# UVB_LED_Array.net
KiCad netlist of a schematic drawn in Altium Designer
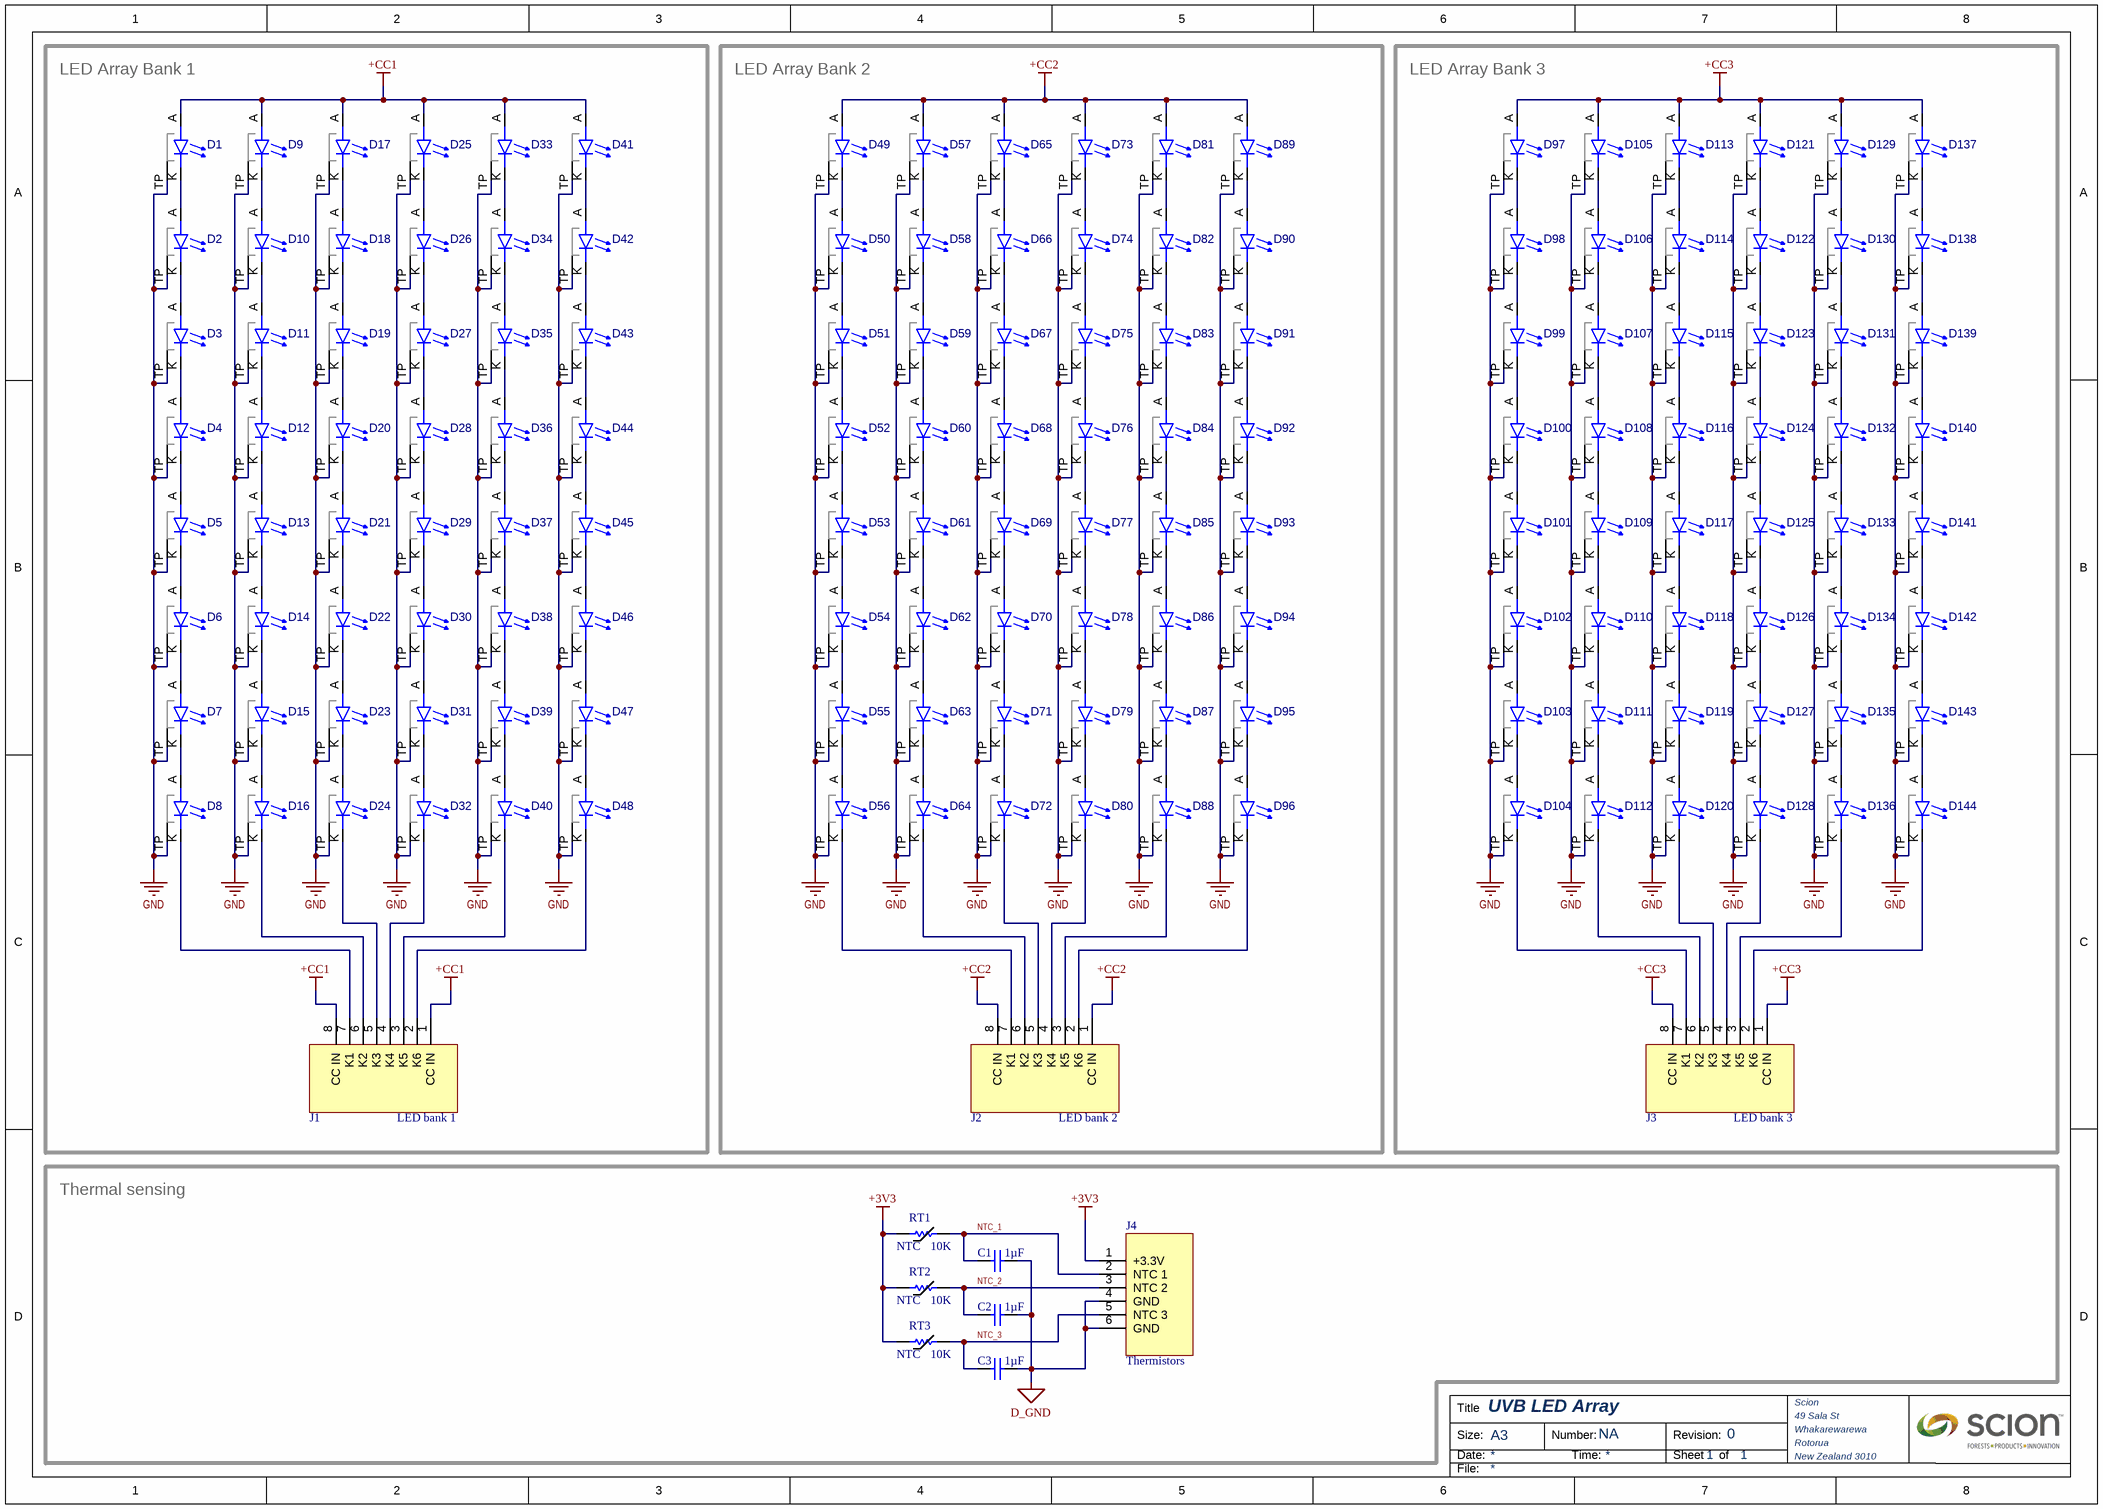
[diagram p0: UVB LED Array.SchDoc]

(export (version "E")
  (design (tool "Eeschema 10.0.6"))
  (components
    (comp (ref "C1")
      (value "1µF")
      (footprint "0603_CAP")
      (description "SMD Capacitor")
      (fields (field (name "Comment") "Capacitor"))
      (libsource (lib "Scion Research") (part "CMP-019-00005-2"))
    )
    (comp (ref "C2")
      (value "1µF")
      (footprint "0603_CAP")
      (description "SMD Capacitor")
      (fields (field (name "Comment") "Capacitor"))
      (libsource (lib "Scion Research") (part "CMP-019-00005-2"))
    )
    (comp (ref "C3")
      (value "1µF")
      (footprint "0603_CAP")
      (description "SMD Capacitor")
      (fields (field (name "Comment") "Capacitor"))
      (libsource (lib "Scion Research") (part "CMP-019-00005-2"))
    )
    (comp (ref "D1")
      (value "3838UVB UV SMD LED")
      (footprint "3838UVB UV SMD LED-Footprint-1")
      (libsource (lib "Scion Research") (part "UVB SMD LED"))
    )
    (comp (ref "D2")
      (value "3838UVB UV SMD LED")
      (footprint "3838UVB UV SMD LED-Footprint-1")
      (libsource (lib "Scion Research") (part "UVB SMD LED"))
    )
    (comp (ref "D3")
      (value "3838UVB UV SMD LED")
      (footprint "3838UVB UV SMD LED-Footprint-1")
      (libsource (lib "Scion Research") (part "UVB SMD LED"))
    )
    (comp (ref "D4")
      (value "3838UVB UV SMD LED")
      (footprint "3838UVB UV SMD LED-Footprint-1")
      (libsource (lib "Scion Research") (part "UVB SMD LED"))
    )
    (comp (ref "D5")
      (value "3838UVB UV SMD LED")
      (footprint "3838UVB UV SMD LED-Footprint-1")
      (libsource (lib "Scion Research") (part "UVB SMD LED"))
    )
    (comp (ref "D6")
      (value "3838UVB UV SMD LED")
      (footprint "3838UVB UV SMD LED-Footprint-1")
      (libsource (lib "Scion Research") (part "UVB SMD LED"))
    )
    (comp (ref "D7")
      (value "3838UVB UV SMD LED")
      (footprint "3838UVB UV SMD LED-Footprint-1")
      (libsource (lib "Scion Research") (part "UVB SMD LED"))
    )
    (comp (ref "D8")
      (value "3838UVB UV SMD LED")
      (footprint "3838UVB UV SMD LED-Footprint-1")
      (libsource (lib "Scion Research") (part "UVB SMD LED"))
    )
    (comp (ref "D9")
      (value "3838UVB UV SMD LED")
      (footprint "3838UVB UV SMD LED-Footprint-1")
      (libsource (lib "Scion Research") (part "UVB SMD LED"))
    )
    (comp (ref "D10")
      (value "3838UVB UV SMD LED")
      (footprint "3838UVB UV SMD LED-Footprint-1")
      (libsource (lib "Scion Research") (part "UVB SMD LED"))
    )
    (comp (ref "D11")
      (value "3838UVB UV SMD LED")
      (footprint "3838UVB UV SMD LED-Footprint-1")
      (libsource (lib "Scion Research") (part "UVB SMD LED"))
    )
    (comp (ref "D12")
      (value "3838UVB UV SMD LED")
      (footprint "3838UVB UV SMD LED-Footprint-1")
      (libsource (lib "Scion Research") (part "UVB SMD LED"))
    )
    (comp (ref "D13")
      (value "3838UVB UV SMD LED")
      (footprint "3838UVB UV SMD LED-Footprint-1")
      (libsource (lib "Scion Research") (part "UVB SMD LED"))
    )
    (comp (ref "D14")
      (value "3838UVB UV SMD LED")
      (footprint "3838UVB UV SMD LED-Footprint-1")
      (libsource (lib "Scion Research") (part "UVB SMD LED"))
    )
    (comp (ref "D15")
      (value "3838UVB UV SMD LED")
      (footprint "3838UVB UV SMD LED-Footprint-1")
      (libsource (lib "Scion Research") (part "UVB SMD LED"))
    )
    (comp (ref "D16")
      (value "3838UVB UV SMD LED")
      (footprint "3838UVB UV SMD LED-Footprint-1")
      (libsource (lib "Scion Research") (part "UVB SMD LED"))
    )
    (comp (ref "D17")
      (value "3838UVB UV SMD LED")
      (footprint "3838UVB UV SMD LED-Footprint-1")
      (libsource (lib "Scion Research") (part "UVB SMD LED"))
    )
    (comp (ref "D18")
      (value "3838UVB UV SMD LED")
      (footprint "3838UVB UV SMD LED-Footprint-1")
      (libsource (lib "Scion Research") (part "UVB SMD LED"))
    )
    (comp (ref "D19")
      (value "3838UVB UV SMD LED")
      (footprint "3838UVB UV SMD LED-Footprint-1")
      (libsource (lib "Scion Research") (part "UVB SMD LED"))
    )
    (comp (ref "D20")
      (value "3838UVB UV SMD LED")
      (footprint "3838UVB UV SMD LED-Footprint-1")
      (libsource (lib "Scion Research") (part "UVB SMD LED"))
    )
    (comp (ref "D21")
      (value "3838UVB UV SMD LED")
      (footprint "3838UVB UV SMD LED-Footprint-1")
      (libsource (lib "Scion Research") (part "UVB SMD LED"))
    )
    (comp (ref "D22")
      (value "3838UVB UV SMD LED")
      (footprint "3838UVB UV SMD LED-Footprint-1")
      (libsource (lib "Scion Research") (part "UVB SMD LED"))
    )
    (comp (ref "D23")
      (value "3838UVB UV SMD LED")
      (footprint "3838UVB UV SMD LED-Footprint-1")
      (libsource (lib "Scion Research") (part "UVB SMD LED"))
    )
    (comp (ref "D24")
      (value "3838UVB UV SMD LED")
      (footprint "3838UVB UV SMD LED-Footprint-1")
      (libsource (lib "Scion Research") (part "UVB SMD LED"))
    )
    (comp (ref "D25")
      (value "3838UVB UV SMD LED")
      (footprint "3838UVB UV SMD LED-Footprint-1")
      (libsource (lib "Scion Research") (part "UVB SMD LED"))
    )
    (comp (ref "D26")
      (value "3838UVB UV SMD LED")
      (footprint "3838UVB UV SMD LED-Footprint-1")
      (libsource (lib "Scion Research") (part "UVB SMD LED"))
    )
    (comp (ref "D27")
      (value "3838UVB UV SMD LED")
      (footprint "3838UVB UV SMD LED-Footprint-1")
      (libsource (lib "Scion Research") (part "UVB SMD LED"))
    )
    (comp (ref "D28")
      (value "3838UVB UV SMD LED")
      (footprint "3838UVB UV SMD LED-Footprint-1")
      (libsource (lib "Scion Research") (part "UVB SMD LED"))
    )
    (comp (ref "D29")
      (value "3838UVB UV SMD LED")
      (footprint "3838UVB UV SMD LED-Footprint-1")
      (libsource (lib "Scion Research") (part "UVB SMD LED"))
    )
    (comp (ref "D30")
      (value "3838UVB UV SMD LED")
      (footprint "3838UVB UV SMD LED-Footprint-1")
      (libsource (lib "Scion Research") (part "UVB SMD LED"))
    )
    (comp (ref "D31")
      (value "3838UVB UV SMD LED")
      (footprint "3838UVB UV SMD LED-Footprint-1")
      (libsource (lib "Scion Research") (part "UVB SMD LED"))
    )
    (comp (ref "D32")
      (value "3838UVB UV SMD LED")
      (footprint "3838UVB UV SMD LED-Footprint-1")
      (libsource (lib "Scion Research") (part "UVB SMD LED"))
    )
    (comp (ref "D33")
      (value "3838UVB UV SMD LED")
      (footprint "3838UVB UV SMD LED-Footprint-1")
      (libsource (lib "Scion Research") (part "UVB SMD LED"))
    )
    (comp (ref "D34")
      (value "3838UVB UV SMD LED")
      (footprint "3838UVB UV SMD LED-Footprint-1")
      (libsource (lib "Scion Research") (part "UVB SMD LED"))
    )
    (comp (ref "D35")
      (value "3838UVB UV SMD LED")
      (footprint "3838UVB UV SMD LED-Footprint-1")
      (libsource (lib "Scion Research") (part "UVB SMD LED"))
    )
    (comp (ref "D36")
      (value "3838UVB UV SMD LED")
      (footprint "3838UVB UV SMD LED-Footprint-1")
      (libsource (lib "Scion Research") (part "UVB SMD LED"))
    )
    (comp (ref "D37")
      (value "3838UVB UV SMD LED")
      (footprint "3838UVB UV SMD LED-Footprint-1")
      (libsource (lib "Scion Research") (part "UVB SMD LED"))
    )
    (comp (ref "D38")
      (value "3838UVB UV SMD LED")
      (footprint "3838UVB UV SMD LED-Footprint-1")
      (libsource (lib "Scion Research") (part "UVB SMD LED"))
    )
    (comp (ref "D39")
      (value "3838UVB UV SMD LED")
      (footprint "3838UVB UV SMD LED-Footprint-1")
      (libsource (lib "Scion Research") (part "UVB SMD LED"))
    )
    (comp (ref "D40")
      (value "3838UVB UV SMD LED")
      (footprint "3838UVB UV SMD LED-Footprint-1")
      (libsource (lib "Scion Research") (part "UVB SMD LED"))
    )
    (comp (ref "D41")
      (value "3838UVB UV SMD LED")
      (footprint "3838UVB UV SMD LED-Footprint-1")
      (libsource (lib "Scion Research") (part "UVB SMD LED"))
    )
    (comp (ref "D42")
      (value "3838UVB UV SMD LED")
      (footprint "3838UVB UV SMD LED-Footprint-1")
      (libsource (lib "Scion Research") (part "UVB SMD LED"))
    )
    (comp (ref "D43")
      (value "3838UVB UV SMD LED")
      (footprint "3838UVB UV SMD LED-Footprint-1")
      (libsource (lib "Scion Research") (part "UVB SMD LED"))
    )
    (comp (ref "D44")
      (value "3838UVB UV SMD LED")
      (footprint "3838UVB UV SMD LED-Footprint-1")
      (libsource (lib "Scion Research") (part "UVB SMD LED"))
    )
    (comp (ref "D45")
      (value "3838UVB UV SMD LED")
      (footprint "3838UVB UV SMD LED-Footprint-1")
      (libsource (lib "Scion Research") (part "UVB SMD LED"))
    )
    (comp (ref "D46")
      (value "3838UVB UV SMD LED")
      (footprint "3838UVB UV SMD LED-Footprint-1")
      (libsource (lib "Scion Research") (part "UVB SMD LED"))
    )
    (comp (ref "D47")
      (value "3838UVB UV SMD LED")
      (footprint "3838UVB UV SMD LED-Footprint-1")
      (libsource (lib "Scion Research") (part "UVB SMD LED"))
    )
    (comp (ref "D48")
      (value "3838UVB UV SMD LED")
      (footprint "3838UVB UV SMD LED-Footprint-1")
      (libsource (lib "Scion Research") (part "UVB SMD LED"))
    )
    (comp (ref "D49")
      (value "3838UVB UV SMD LED")
      (footprint "3838UVB UV SMD LED-Footprint-1")
      (libsource (lib "Scion Research") (part "UVB SMD LED"))
    )
    (comp (ref "D50")
      (value "3838UVB UV SMD LED")
      (footprint "3838UVB UV SMD LED-Footprint-1")
      (libsource (lib "Scion Research") (part "UVB SMD LED"))
    )
    (comp (ref "D51")
      (value "3838UVB UV SMD LED")
      (footprint "3838UVB UV SMD LED-Footprint-1")
      (libsource (lib "Scion Research") (part "UVB SMD LED"))
    )
    (comp (ref "D52")
      (value "3838UVB UV SMD LED")
      (footprint "3838UVB UV SMD LED-Footprint-1")
      (libsource (lib "Scion Research") (part "UVB SMD LED"))
    )
    (comp (ref "D53")
      (value "3838UVB UV SMD LED")
      (footprint "3838UVB UV SMD LED-Footprint-1")
      (libsource (lib "Scion Research") (part "UVB SMD LED"))
    )
    (comp (ref "D54")
      (value "3838UVB UV SMD LED")
      (footprint "3838UVB UV SMD LED-Footprint-1")
      (libsource (lib "Scion Research") (part "UVB SMD LED"))
    )
    (comp (ref "D55")
      (value "3838UVB UV SMD LED")
      (footprint "3838UVB UV SMD LED-Footprint-1")
      (libsource (lib "Scion Research") (part "UVB SMD LED"))
    )
    (comp (ref "D56")
      (value "3838UVB UV SMD LED")
      (footprint "3838UVB UV SMD LED-Footprint-1")
      (libsource (lib "Scion Research") (part "UVB SMD LED"))
    )
    (comp (ref "D57")
      (value "3838UVB UV SMD LED")
      (footprint "3838UVB UV SMD LED-Footprint-1")
      (libsource (lib "Scion Research") (part "UVB SMD LED"))
    )
    (comp (ref "D58")
      (value "3838UVB UV SMD LED")
      (footprint "3838UVB UV SMD LED-Footprint-1")
      (libsource (lib "Scion Research") (part "UVB SMD LED"))
    )
    (comp (ref "D59")
      (value "3838UVB UV SMD LED")
      (footprint "3838UVB UV SMD LED-Footprint-1")
      (libsource (lib "Scion Research") (part "UVB SMD LED"))
    )
    (comp (ref "D60")
      (value "3838UVB UV SMD LED")
      (footprint "3838UVB UV SMD LED-Footprint-1")
      (libsource (lib "Scion Research") (part "UVB SMD LED"))
    )
    (comp (ref "D61")
      (value "3838UVB UV SMD LED")
      (footprint "3838UVB UV SMD LED-Footprint-1")
      (libsource (lib "Scion Research") (part "UVB SMD LED"))
    )
    (comp (ref "D62")
      (value "3838UVB UV SMD LED")
      (footprint "3838UVB UV SMD LED-Footprint-1")
      (libsource (lib "Scion Research") (part "UVB SMD LED"))
    )
    (comp (ref "D63")
      (value "3838UVB UV SMD LED")
      (footprint "3838UVB UV SMD LED-Footprint-1")
      (libsource (lib "Scion Research") (part "UVB SMD LED"))
    )
    (comp (ref "D64")
      (value "3838UVB UV SMD LED")
      (footprint "3838UVB UV SMD LED-Footprint-1")
      (libsource (lib "Scion Research") (part "UVB SMD LED"))
    )
    (comp (ref "D65")
      (value "3838UVB UV SMD LED")
      (footprint "3838UVB UV SMD LED-Footprint-1")
      (libsource (lib "Scion Research") (part "UVB SMD LED"))
    )
    (comp (ref "D66")
      (value "3838UVB UV SMD LED")
      (footprint "3838UVB UV SMD LED-Footprint-1")
      (libsource (lib "Scion Research") (part "UVB SMD LED"))
    )
    (comp (ref "D67")
      (value "3838UVB UV SMD LED")
      (footprint "3838UVB UV SMD LED-Footprint-1")
      (libsource (lib "Scion Research") (part "UVB SMD LED"))
    )
    (comp (ref "D68")
      (value "3838UVB UV SMD LED")
      (footprint "3838UVB UV SMD LED-Footprint-1")
      (libsource (lib "Scion Research") (part "UVB SMD LED"))
    )
    (comp (ref "D69")
      (value "3838UVB UV SMD LED")
      (footprint "3838UVB UV SMD LED-Footprint-1")
      (libsource (lib "Scion Research") (part "UVB SMD LED"))
    )
    (comp (ref "D70")
      (value "3838UVB UV SMD LED")
      (footprint "3838UVB UV SMD LED-Footprint-1")
      (libsource (lib "Scion Research") (part "UVB SMD LED"))
    )
    (comp (ref "D71")
      (value "3838UVB UV SMD LED")
      (footprint "3838UVB UV SMD LED-Footprint-1")
      (libsource (lib "Scion Research") (part "UVB SMD LED"))
    )
    (comp (ref "D72")
      (value "3838UVB UV SMD LED")
      (footprint "3838UVB UV SMD LED-Footprint-1")
      (libsource (lib "Scion Research") (part "UVB SMD LED"))
    )
    (comp (ref "D73")
      (value "3838UVB UV SMD LED")
      (footprint "3838UVB UV SMD LED-Footprint-1")
      (libsource (lib "Scion Research") (part "UVB SMD LED"))
    )
    (comp (ref "D74")
      (value "3838UVB UV SMD LED")
      (footprint "3838UVB UV SMD LED-Footprint-1")
      (libsource (lib "Scion Research") (part "UVB SMD LED"))
    )
    (comp (ref "D75")
      (value "3838UVB UV SMD LED")
      (footprint "3838UVB UV SMD LED-Footprint-1")
      (libsource (lib "Scion Research") (part "UVB SMD LED"))
    )
    (comp (ref "D76")
      (value "3838UVB UV SMD LED")
      (footprint "3838UVB UV SMD LED-Footprint-1")
      (libsource (lib "Scion Research") (part "UVB SMD LED"))
    )
    (comp (ref "D77")
      (value "3838UVB UV SMD LED")
      (footprint "3838UVB UV SMD LED-Footprint-1")
      (libsource (lib "Scion Research") (part "UVB SMD LED"))
    )
    (comp (ref "D78")
      (value "3838UVB UV SMD LED")
      (footprint "3838UVB UV SMD LED-Footprint-1")
      (libsource (lib "Scion Research") (part "UVB SMD LED"))
    )
    (comp (ref "D79")
      (value "3838UVB UV SMD LED")
      (footprint "3838UVB UV SMD LED-Footprint-1")
      (libsource (lib "Scion Research") (part "UVB SMD LED"))
    )
    (comp (ref "D80")
      (value "3838UVB UV SMD LED")
      (footprint "3838UVB UV SMD LED-Footprint-1")
      (libsource (lib "Scion Research") (part "UVB SMD LED"))
    )
    (comp (ref "D81")
      (value "3838UVB UV SMD LED")
      (footprint "3838UVB UV SMD LED-Footprint-1")
      (libsource (lib "Scion Research") (part "UVB SMD LED"))
    )
    (comp (ref "D82")
      (value "3838UVB UV SMD LED")
      (footprint "3838UVB UV SMD LED-Footprint-1")
      (libsource (lib "Scion Research") (part "UVB SMD LED"))
    )
    (comp (ref "D83")
      (value "3838UVB UV SMD LED")
      (footprint "3838UVB UV SMD LED-Footprint-1")
      (libsource (lib "Scion Research") (part "UVB SMD LED"))
    )
    (comp (ref "D84")
      (value "3838UVB UV SMD LED")
      (footprint "3838UVB UV SMD LED-Footprint-1")
      (libsource (lib "Scion Research") (part "UVB SMD LED"))
    )
    (comp (ref "D85")
      (value "3838UVB UV SMD LED")
      (footprint "3838UVB UV SMD LED-Footprint-1")
      (libsource (lib "Scion Research") (part "UVB SMD LED"))
    )
    (comp (ref "D86")
      (value "3838UVB UV SMD LED")
      (footprint "3838UVB UV SMD LED-Footprint-1")
      (libsource (lib "Scion Research") (part "UVB SMD LED"))
    )
    (comp (ref "D87")
      (value "3838UVB UV SMD LED")
      (footprint "3838UVB UV SMD LED-Footprint-1")
      (libsource (lib "Scion Research") (part "UVB SMD LED"))
    )
    (comp (ref "D88")
      (value "3838UVB UV SMD LED")
      (footprint "3838UVB UV SMD LED-Footprint-1")
      (libsource (lib "Scion Research") (part "UVB SMD LED"))
    )
    (comp (ref "D89")
      (value "3838UVB UV SMD LED")
      (footprint "3838UVB UV SMD LED-Footprint-1")
      (libsource (lib "Scion Research") (part "UVB SMD LED"))
    )
    (comp (ref "D90")
      (value "3838UVB UV SMD LED")
      (footprint "3838UVB UV SMD LED-Footprint-1")
      (libsource (lib "Scion Research") (part "UVB SMD LED"))
    )
    (comp (ref "D91")
      (value "3838UVB UV SMD LED")
      (footprint "3838UVB UV SMD LED-Footprint-1")
      (libsource (lib "Scion Research") (part "UVB SMD LED"))
    )
    (comp (ref "D92")
      (value "3838UVB UV SMD LED")
      (footprint "3838UVB UV SMD LED-Footprint-1")
      (libsource (lib "Scion Research") (part "UVB SMD LED"))
    )
    (comp (ref "D93")
      (value "3838UVB UV SMD LED")
      (footprint "3838UVB UV SMD LED-Footprint-1")
      (libsource (lib "Scion Research") (part "UVB SMD LED"))
    )
    (comp (ref "D94")
      (value "3838UVB UV SMD LED")
      (footprint "3838UVB UV SMD LED-Footprint-1")
      (libsource (lib "Scion Research") (part "UVB SMD LED"))
    )
    (comp (ref "D95")
      (value "3838UVB UV SMD LED")
      (footprint "3838UVB UV SMD LED-Footprint-1")
      (libsource (lib "Scion Research") (part "UVB SMD LED"))
    )
    (comp (ref "D96")
      (value "3838UVB UV SMD LED")
      (footprint "3838UVB UV SMD LED-Footprint-1")
      (libsource (lib "Scion Research") (part "UVB SMD LED"))
    )
    (comp (ref "D97")
      (value "3838UVB UV SMD LED")
      (footprint "3838UVB UV SMD LED-Footprint-1")
      (libsource (lib "Scion Research") (part "UVB SMD LED"))
    )
    (comp (ref "D98")
      (value "3838UVB UV SMD LED")
      (footprint "3838UVB UV SMD LED-Footprint-1")
      (libsource (lib "Scion Research") (part "UVB SMD LED"))
    )
    (comp (ref "D99")
      (value "3838UVB UV SMD LED")
      (footprint "3838UVB UV SMD LED-Footprint-1")
      (libsource (lib "Scion Research") (part "UVB SMD LED"))
    )
    (comp (ref "D100")
      (value "3838UVB UV SMD LED")
      (footprint "3838UVB UV SMD LED-Footprint-1")
      (libsource (lib "Scion Research") (part "UVB SMD LED"))
    )
    (comp (ref "D101")
      (value "3838UVB UV SMD LED")
      (footprint "3838UVB UV SMD LED-Footprint-1")
      (libsource (lib "Scion Research") (part "UVB SMD LED"))
    )
    (comp (ref "D102")
      (value "3838UVB UV SMD LED")
      (footprint "3838UVB UV SMD LED-Footprint-1")
      (libsource (lib "Scion Research") (part "UVB SMD LED"))
    )
    (comp (ref "D103")
      (value "3838UVB UV SMD LED")
      (footprint "3838UVB UV SMD LED-Footprint-1")
      (libsource (lib "Scion Research") (part "UVB SMD LED"))
    )
    (comp (ref "D104")
      (value "3838UVB UV SMD LED")
      (footprint "3838UVB UV SMD LED-Footprint-1")
      (libsource (lib "Scion Research") (part "UVB SMD LED"))
    )
    (comp (ref "D105")
      (value "3838UVB UV SMD LED")
      (footprint "3838UVB UV SMD LED-Footprint-1")
      (libsource (lib "Scion Research") (part "UVB SMD LED"))
    )
    (comp (ref "D106")
      (value "3838UVB UV SMD LED")
      (footprint "3838UVB UV SMD LED-Footprint-1")
      (libsource (lib "Scion Research") (part "UVB SMD LED"))
    )
    (comp (ref "D107")
      (value "3838UVB UV SMD LED")
      (footprint "3838UVB UV SMD LED-Footprint-1")
      (libsource (lib "Scion Research") (part "UVB SMD LED"))
    )
    (comp (ref "D108")
      (value "3838UVB UV SMD LED")
      (footprint "3838UVB UV SMD LED-Footprint-1")
      (libsource (lib "Scion Research") (part "UVB SMD LED"))
    )
    (comp (ref "D109")
      (value "3838UVB UV SMD LED")
      (footprint "3838UVB UV SMD LED-Footprint-1")
      (libsource (lib "Scion Research") (part "UVB SMD LED"))
    )
    (comp (ref "D110")
      (value "3838UVB UV SMD LED")
      (footprint "3838UVB UV SMD LED-Footprint-1")
      (libsource (lib "Scion Research") (part "UVB SMD LED"))
    )
    (comp (ref "D111")
      (value "3838UVB UV SMD LED")
      (footprint "3838UVB UV SMD LED-Footprint-1")
      (libsource (lib "Scion Research") (part "UVB SMD LED"))
    )
    (comp (ref "D112")
      (value "3838UVB UV SMD LED")
      (footprint "3838UVB UV SMD LED-Footprint-1")
      (libsource (lib "Scion Research") (part "UVB SMD LED"))
    )
    (comp (ref "D113")
      (value "3838UVB UV SMD LED")
      (footprint "3838UVB UV SMD LED-Footprint-1")
      (libsource (lib "Scion Research") (part "UVB SMD LED"))
    )
    (comp (ref "D114")
      (value "3838UVB UV SMD LED")
      (footprint "3838UVB UV SMD LED-Footprint-1")
      (libsource (lib "Scion Research") (part "UVB SMD LED"))
    )
    (comp (ref "D115")
      (value "3838UVB UV SMD LED")
      (footprint "3838UVB UV SMD LED-Footprint-1")
      (libsource (lib "Scion Research") (part "UVB SMD LED"))
    )
    (comp (ref "D116")
      (value "3838UVB UV SMD LED")
      (footprint "3838UVB UV SMD LED-Footprint-1")
      (libsource (lib "Scion Research") (part "UVB SMD LED"))
    )
    (comp (ref "D117")
      (value "3838UVB UV SMD LED")
      (footprint "3838UVB UV SMD LED-Footprint-1")
      (libsource (lib "Scion Research") (part "UVB SMD LED"))
    )
    (comp (ref "D118")
      (value "3838UVB UV SMD LED")
      (footprint "3838UVB UV SMD LED-Footprint-1")
      (libsource (lib "Scion Research") (part "UVB SMD LED"))
    )
    (comp (ref "D119")
      (value "3838UVB UV SMD LED")
      (footprint "3838UVB UV SMD LED-Footprint-1")
      (libsource (lib "Scion Research") (part "UVB SMD LED"))
    )
    (comp (ref "D120")
      (value "3838UVB UV SMD LED")
      (footprint "3838UVB UV SMD LED-Footprint-1")
      (libsource (lib "Scion Research") (part "UVB SMD LED"))
    )
    (comp (ref "D121")
      (value "3838UVB UV SMD LED")
      (footprint "3838UVB UV SMD LED-Footprint-1")
      (libsource (lib "Scion Research") (part "UVB SMD LED"))
    )
    (comp (ref "D122")
      (value "3838UVB UV SMD LED")
      (footprint "3838UVB UV SMD LED-Footprint-1")
      (libsource (lib "Scion Research") (part "UVB SMD LED"))
    )
    (comp (ref "D123")
      (value "3838UVB UV SMD LED")
      (footprint "3838UVB UV SMD LED-Footprint-1")
      (libsource (lib "Scion Research") (part "UVB SMD LED"))
    )
    (comp (ref "D124")
      (value "3838UVB UV SMD LED")
      (footprint "3838UVB UV SMD LED-Footprint-1")
      (libsource (lib "Scion Research") (part "UVB SMD LED"))
    )
    (comp (ref "D125")
      (value "3838UVB UV SMD LED")
      (footprint "3838UVB UV SMD LED-Footprint-1")
      (libsource (lib "Scion Research") (part "UVB SMD LED"))
    )
    (comp (ref "D126")
      (value "3838UVB UV SMD LED")
      (footprint "3838UVB UV SMD LED-Footprint-1")
      (libsource (lib "Scion Research") (part "UVB SMD LED"))
    )
    (comp (ref "D127")
      (value "3838UVB UV SMD LED")
      (footprint "3838UVB UV SMD LED-Footprint-1")
      (libsource (lib "Scion Research") (part "UVB SMD LED"))
    )
    (comp (ref "D128")
      (value "3838UVB UV SMD LED")
      (footprint "3838UVB UV SMD LED-Footprint-1")
      (libsource (lib "Scion Research") (part "UVB SMD LED"))
    )
    (comp (ref "D129")
      (value "3838UVB UV SMD LED")
      (footprint "3838UVB UV SMD LED-Footprint-1")
      (libsource (lib "Scion Research") (part "UVB SMD LED"))
    )
    (comp (ref "D130")
      (value "3838UVB UV SMD LED")
      (footprint "3838UVB UV SMD LED-Footprint-1")
      (libsource (lib "Scion Research") (part "UVB SMD LED"))
    )
    (comp (ref "D131")
      (value "3838UVB UV SMD LED")
      (footprint "3838UVB UV SMD LED-Footprint-1")
      (libsource (lib "Scion Research") (part "UVB SMD LED"))
    )
    (comp (ref "D132")
      (value "3838UVB UV SMD LED")
      (footprint "3838UVB UV SMD LED-Footprint-1")
      (libsource (lib "Scion Research") (part "UVB SMD LED"))
    )
    (comp (ref "D133")
      (value "3838UVB UV SMD LED")
      (footprint "3838UVB UV SMD LED-Footprint-1")
      (libsource (lib "Scion Research") (part "UVB SMD LED"))
    )
    (comp (ref "D134")
      (value "3838UVB UV SMD LED")
      (footprint "3838UVB UV SMD LED-Footprint-1")
      (libsource (lib "Scion Research") (part "UVB SMD LED"))
    )
    (comp (ref "D135")
      (value "3838UVB UV SMD LED")
      (footprint "3838UVB UV SMD LED-Footprint-1")
      (libsource (lib "Scion Research") (part "UVB SMD LED"))
    )
    (comp (ref "D136")
      (value "3838UVB UV SMD LED")
      (footprint "3838UVB UV SMD LED-Footprint-1")
      (libsource (lib "Scion Research") (part "UVB SMD LED"))
    )
    (comp (ref "D137")
      (value "3838UVB UV SMD LED")
      (footprint "3838UVB UV SMD LED-Footprint-1")
      (libsource (lib "Scion Research") (part "UVB SMD LED"))
    )
    (comp (ref "D138")
      (value "3838UVB UV SMD LED")
      (footprint "3838UVB UV SMD LED-Footprint-1")
      (libsource (lib "Scion Research") (part "UVB SMD LED"))
    )
    (comp (ref "D139")
      (value "3838UVB UV SMD LED")
      (footprint "3838UVB UV SMD LED-Footprint-1")
      (libsource (lib "Scion Research") (part "UVB SMD LED"))
    )
    (comp (ref "D140")
      (value "3838UVB UV SMD LED")
      (footprint "3838UVB UV SMD LED-Footprint-1")
      (libsource (lib "Scion Research") (part "UVB SMD LED"))
    )
    (comp (ref "D141")
      (value "3838UVB UV SMD LED")
      (footprint "3838UVB UV SMD LED-Footprint-1")
      (libsource (lib "Scion Research") (part "UVB SMD LED"))
    )
    (comp (ref "D142")
      (value "3838UVB UV SMD LED")
      (footprint "3838UVB UV SMD LED-Footprint-1")
      (libsource (lib "Scion Research") (part "UVB SMD LED"))
    )
    (comp (ref "D143")
      (value "3838UVB UV SMD LED")
      (footprint "3838UVB UV SMD LED-Footprint-1")
      (libsource (lib "Scion Research") (part "UVB SMD LED"))
    )
    (comp (ref "D144")
      (value "3838UVB UV SMD LED")
      (footprint "3838UVB UV SMD LED-Footprint-1")
      (libsource (lib "Scion Research") (part "UVB SMD LED"))
    )
    (comp (ref "J1")
      (value "LED bank 1")
      (footprint "8P Clik-MATE 1.5mm INVERTED")
      (description "8 Pin Connector")
      (libsource (lib "Scion Research") (part "CMP-002-00084-5"))
    )
    (comp (ref "J2")
      (value "LED bank 2")
      (footprint "8P Clik-MATE 1.5mm INVERTED")
      (description "8 Pin Connector")
      (libsource (lib "Scion Research") (part "CMP-002-00084-5"))
    )
    (comp (ref "J3")
      (value "LED bank 3")
      (footprint "8P Clik-MATE 1.5mm INVERTED")
      (description "8 Pin Connector")
      (libsource (lib "Scion Research") (part "CMP-002-00084-5"))
    )
    (comp (ref "J4")
      (value "Thermistors")
      (footprint "6P Clik-MATE 1.5mm INVERTED")
      (description "6 Pin Connector")
      (libsource (lib "Scion Research") (part "CMP-002-00081-5"))
    )
    (comp (ref "RT1")
      (value "NTC")
      (footprint "0603_THERM")
      (description "Thermistor")
      (fields (field (name "ALTIUM_VALUE") "10K"))
      (libsource (lib "Scion Research") (part "CMP-004-0039-3"))
    )
    (comp (ref "RT2")
      (value "NTC")
      (footprint "0603_THERM")
      (description "Thermistor")
      (fields (field (name "ALTIUM_VALUE") "10K"))
      (libsource (lib "Scion Research") (part "CMP-004-0039-3"))
    )
    (comp (ref "RT3")
      (value "NTC")
      (footprint "0603_THERM")
      (description "Thermistor")
      (fields (field (name "ALTIUM_VALUE") "10K"))
      (libsource (lib "Scion Research") (part "CMP-004-0039-3"))
    )
  )
  (nets
    (net (code "1") (name "+3V3") (class "Default")
      (node (ref "J4") (pin "1") (pinfunction "+3.3V_1") (pintype "passive"))
      (node (ref "RT1") (pin "1") (pinfunction "1_1") (pintype "passive"))
      (node (ref "RT2") (pin "1") (pinfunction "1_1") (pintype "passive"))
      (node (ref "RT3") (pin "1") (pinfunction "1_1") (pintype "passive"))
    )
    (net (code "2") (name "+CC1") (class "Default")
      (node (ref "D1") (pin "A") (pinfunction "A_A") (pintype "passive"))
      (node (ref "D17") (pin "A") (pinfunction "A_A") (pintype "passive"))
      (node (ref "D25") (pin "A") (pinfunction "A_A") (pintype "passive"))
      (node (ref "D33") (pin "A") (pinfunction "A_A") (pintype "passive"))
      (node (ref "D41") (pin "A") (pinfunction "A_A") (pintype "passive"))
      (node (ref "D9") (pin "A") (pinfunction "A_A") (pintype "passive"))
      (node (ref "J1") (pin "1") (pinfunction "CC_IN_1") (pintype "passive"))
      (node (ref "J1") (pin "8") (pinfunction "CC_IN_8") (pintype "passive"))
    )
    (net (code "3") (name "+CC2") (class "Default")
      (node (ref "D49") (pin "A") (pinfunction "A_A") (pintype "passive"))
      (node (ref "D57") (pin "A") (pinfunction "A_A") (pintype "passive"))
      (node (ref "D65") (pin "A") (pinfunction "A_A") (pintype "passive"))
      (node (ref "D73") (pin "A") (pinfunction "A_A") (pintype "passive"))
      (node (ref "D81") (pin "A") (pinfunction "A_A") (pintype "passive"))
      (node (ref "D89") (pin "A") (pinfunction "A_A") (pintype "passive"))
      (node (ref "J2") (pin "1") (pinfunction "CC_IN_1") (pintype "passive"))
      (node (ref "J2") (pin "8") (pinfunction "CC_IN_8") (pintype "passive"))
    )
    (net (code "4") (name "+CC3") (class "Default")
      (node (ref "D105") (pin "A") (pinfunction "A_A") (pintype "passive"))
      (node (ref "D113") (pin "A") (pinfunction "A_A") (pintype "passive"))
      (node (ref "D121") (pin "A") (pinfunction "A_A") (pintype "passive"))
      (node (ref "D129") (pin "A") (pinfunction "A_A") (pintype "passive"))
      (node (ref "D137") (pin "A") (pinfunction "A_A") (pintype "passive"))
      (node (ref "D97") (pin "A") (pinfunction "A_A") (pintype "passive"))
      (node (ref "J3") (pin "1") (pinfunction "CC_IN_1") (pintype "passive"))
      (node (ref "J3") (pin "8") (pinfunction "CC_IN_8") (pintype "passive"))
    )
    (net (code "5") (name "/NTC_1") (class "Default")
      (node (ref "C1") (pin "2") (pinfunction "2_2") (pintype "passive"))
      (node (ref "J4") (pin "2") (pinfunction "NTC_1_2") (pintype "passive"))
      (node (ref "RT1") (pin "2") (pinfunction "2_2") (pintype "passive"))
    )
    (net (code "6") (name "/NTC_2") (class "Default")
      (node (ref "C2") (pin "2") (pinfunction "2_2") (pintype "passive"))
      (node (ref "J4") (pin "3") (pinfunction "NTC_2_3") (pintype "passive"))
      (node (ref "RT2") (pin "2") (pinfunction "2_2") (pintype "passive"))
    )
    (net (code "7") (name "/NTC_3") (class "Default")
      (node (ref "C3") (pin "2") (pinfunction "2_2") (pintype "passive"))
      (node (ref "J4") (pin "5") (pinfunction "NTC_3_5") (pintype "passive"))
      (node (ref "RT3") (pin "2") (pinfunction "2_2") (pintype "passive"))
    )
    (net (code "8") (name "D_GND") (class "Default")
      (node (ref "C1") (pin "1") (pinfunction "1_1") (pintype "passive"))
      (node (ref "C2") (pin "1") (pinfunction "1_1") (pintype "passive"))
      (node (ref "C3") (pin "1") (pinfunction "1_1") (pintype "passive"))
      (node (ref "J4") (pin "4") (pinfunction "GND_4") (pintype "passive"))
      (node (ref "J4") (pin "6") (pinfunction "GND_6") (pintype "passive"))
    )
    (net (code "9") (name "GND") (class "Default")
      (node (ref "D1") (pin "TP") (pinfunction "Pad_TP") (pintype "passive"))
      (node (ref "D10") (pin "TP") (pinfunction "Pad_TP") (pintype "passive"))
      (node (ref "D100") (pin "TP") (pinfunction "Pad_TP") (pintype "passive"))
      (node (ref "D101") (pin "TP") (pinfunction "Pad_TP") (pintype "passive"))
      (node (ref "D102") (pin "TP") (pinfunction "Pad_TP") (pintype "passive"))
      (node (ref "D103") (pin "TP") (pinfunction "Pad_TP") (pintype "passive"))
      (node (ref "D104") (pin "TP") (pinfunction "Pad_TP") (pintype "passive"))
      (node (ref "D105") (pin "TP") (pinfunction "Pad_TP") (pintype "passive"))
      (node (ref "D106") (pin "TP") (pinfunction "Pad_TP") (pintype "passive"))
      (node (ref "D107") (pin "TP") (pinfunction "Pad_TP") (pintype "passive"))
      (node (ref "D108") (pin "TP") (pinfunction "Pad_TP") (pintype "passive"))
      (node (ref "D109") (pin "TP") (pinfunction "Pad_TP") (pintype "passive"))
      (node (ref "D11") (pin "TP") (pinfunction "Pad_TP") (pintype "passive"))
      (node (ref "D110") (pin "TP") (pinfunction "Pad_TP") (pintype "passive"))
      (node (ref "D111") (pin "TP") (pinfunction "Pad_TP") (pintype "passive"))
      (node (ref "D112") (pin "TP") (pinfunction "Pad_TP") (pintype "passive"))
      (node (ref "D113") (pin "TP") (pinfunction "Pad_TP") (pintype "passive"))
      (node (ref "D114") (pin "TP") (pinfunction "Pad_TP") (pintype "passive"))
      (node (ref "D115") (pin "TP") (pinfunction "Pad_TP") (pintype "passive"))
      (node (ref "D116") (pin "TP") (pinfunction "Pad_TP") (pintype "passive"))
      (node (ref "D117") (pin "TP") (pinfunction "Pad_TP") (pintype "passive"))
      (node (ref "D118") (pin "TP") (pinfunction "Pad_TP") (pintype "passive"))
      (node (ref "D119") (pin "TP") (pinfunction "Pad_TP") (pintype "passive"))
      (node (ref "D12") (pin "TP") (pinfunction "Pad_TP") (pintype "passive"))
      (node (ref "D120") (pin "TP") (pinfunction "Pad_TP") (pintype "passive"))
      (node (ref "D121") (pin "TP") (pinfunction "Pad_TP") (pintype "passive"))
      (node (ref "D122") (pin "TP") (pinfunction "Pad_TP") (pintype "passive"))
      (node (ref "D123") (pin "TP") (pinfunction "Pad_TP") (pintype "passive"))
      (node (ref "D124") (pin "TP") (pinfunction "Pad_TP") (pintype "passive"))
      (node (ref "D125") (pin "TP") (pinfunction "Pad_TP") (pintype "passive"))
      (node (ref "D126") (pin "TP") (pinfunction "Pad_TP") (pintype "passive"))
      (node (ref "D127") (pin "TP") (pinfunction "Pad_TP") (pintype "passive"))
      (node (ref "D128") (pin "TP") (pinfunction "Pad_TP") (pintype "passive"))
      (node (ref "D129") (pin "TP") (pinfunction "Pad_TP") (pintype "passive"))
      (node (ref "D13") (pin "TP") (pinfunction "Pad_TP") (pintype "passive"))
      (node (ref "D130") (pin "TP") (pinfunction "Pad_TP") (pintype "passive"))
      (node (ref "D131") (pin "TP") (pinfunction "Pad_TP") (pintype "passive"))
      (node (ref "D132") (pin "TP") (pinfunction "Pad_TP") (pintype "passive"))
      (node (ref "D133") (pin "TP") (pinfunction "Pad_TP") (pintype "passive"))
      (node (ref "D134") (pin "TP") (pinfunction "Pad_TP") (pintype "passive"))
      (node (ref "D135") (pin "TP") (pinfunction "Pad_TP") (pintype "passive"))
      (node (ref "D136") (pin "TP") (pinfunction "Pad_TP") (pintype "passive"))
      (node (ref "D137") (pin "TP") (pinfunction "Pad_TP") (pintype "passive"))
      (node (ref "D138") (pin "TP") (pinfunction "Pad_TP") (pintype "passive"))
      (node (ref "D139") (pin "TP") (pinfunction "Pad_TP") (pintype "passive"))
      (node (ref "D14") (pin "TP") (pinfunction "Pad_TP") (pintype "passive"))
      (node (ref "D140") (pin "TP") (pinfunction "Pad_TP") (pintype "passive"))
      (node (ref "D141") (pin "TP") (pinfunction "Pad_TP") (pintype "passive"))
      (node (ref "D142") (pin "TP") (pinfunction "Pad_TP") (pintype "passive"))
      (node (ref "D143") (pin "TP") (pinfunction "Pad_TP") (pintype "passive"))
      (node (ref "D144") (pin "TP") (pinfunction "Pad_TP") (pintype "passive"))
      (node (ref "D15") (pin "TP") (pinfunction "Pad_TP") (pintype "passive"))
      (node (ref "D16") (pin "TP") (pinfunction "Pad_TP") (pintype "passive"))
      (node (ref "D17") (pin "TP") (pinfunction "Pad_TP") (pintype "passive"))
      (node (ref "D18") (pin "TP") (pinfunction "Pad_TP") (pintype "passive"))
      (node (ref "D19") (pin "TP") (pinfunction "Pad_TP") (pintype "passive"))
      (node (ref "D2") (pin "TP") (pinfunction "Pad_TP") (pintype "passive"))
      (node (ref "D20") (pin "TP") (pinfunction "Pad_TP") (pintype "passive"))
      (node (ref "D21") (pin "TP") (pinfunction "Pad_TP") (pintype "passive"))
      (node (ref "D22") (pin "TP") (pinfunction "Pad_TP") (pintype "passive"))
      (node (ref "D23") (pin "TP") (pinfunction "Pad_TP") (pintype "passive"))
      (node (ref "D24") (pin "TP") (pinfunction "Pad_TP") (pintype "passive"))
      (node (ref "D25") (pin "TP") (pinfunction "Pad_TP") (pintype "passive"))
      (node (ref "D26") (pin "TP") (pinfunction "Pad_TP") (pintype "passive"))
      (node (ref "D27") (pin "TP") (pinfunction "Pad_TP") (pintype "passive"))
      (node (ref "D28") (pin "TP") (pinfunction "Pad_TP") (pintype "passive"))
      (node (ref "D29") (pin "TP") (pinfunction "Pad_TP") (pintype "passive"))
      (node (ref "D3") (pin "TP") (pinfunction "Pad_TP") (pintype "passive"))
      (node (ref "D30") (pin "TP") (pinfunction "Pad_TP") (pintype "passive"))
      (node (ref "D31") (pin "TP") (pinfunction "Pad_TP") (pintype "passive"))
      (node (ref "D32") (pin "TP") (pinfunction "Pad_TP") (pintype "passive"))
      (node (ref "D33") (pin "TP") (pinfunction "Pad_TP") (pintype "passive"))
      (node (ref "D34") (pin "TP") (pinfunction "Pad_TP") (pintype "passive"))
      (node (ref "D35") (pin "TP") (pinfunction "Pad_TP") (pintype "passive"))
      (node (ref "D36") (pin "TP") (pinfunction "Pad_TP") (pintype "passive"))
      (node (ref "D37") (pin "TP") (pinfunction "Pad_TP") (pintype "passive"))
      (node (ref "D38") (pin "TP") (pinfunction "Pad_TP") (pintype "passive"))
      (node (ref "D39") (pin "TP") (pinfunction "Pad_TP") (pintype "passive"))
      (node (ref "D4") (pin "TP") (pinfunction "Pad_TP") (pintype "passive"))
      (node (ref "D40") (pin "TP") (pinfunction "Pad_TP") (pintype "passive"))
      (node (ref "D41") (pin "TP") (pinfunction "Pad_TP") (pintype "passive"))
      (node (ref "D42") (pin "TP") (pinfunction "Pad_TP") (pintype "passive"))
      (node (ref "D43") (pin "TP") (pinfunction "Pad_TP") (pintype "passive"))
      (node (ref "D44") (pin "TP") (pinfunction "Pad_TP") (pintype "passive"))
      (node (ref "D45") (pin "TP") (pinfunction "Pad_TP") (pintype "passive"))
      (node (ref "D46") (pin "TP") (pinfunction "Pad_TP") (pintype "passive"))
      (node (ref "D47") (pin "TP") (pinfunction "Pad_TP") (pintype "passive"))
      (node (ref "D48") (pin "TP") (pinfunction "Pad_TP") (pintype "passive"))
      (node (ref "D49") (pin "TP") (pinfunction "Pad_TP") (pintype "passive"))
      (node (ref "D5") (pin "TP") (pinfunction "Pad_TP") (pintype "passive"))
      (node (ref "D50") (pin "TP") (pinfunction "Pad_TP") (pintype "passive"))
      (node (ref "D51") (pin "TP") (pinfunction "Pad_TP") (pintype "passive"))
      (node (ref "D52") (pin "TP") (pinfunction "Pad_TP") (pintype "passive"))
      (node (ref "D53") (pin "TP") (pinfunction "Pad_TP") (pintype "passive"))
      (node (ref "D54") (pin "TP") (pinfunction "Pad_TP") (pintype "passive"))
      (node (ref "D55") (pin "TP") (pinfunction "Pad_TP") (pintype "passive"))
      (node (ref "D56") (pin "TP") (pinfunction "Pad_TP") (pintype "passive"))
      (node (ref "D57") (pin "TP") (pinfunction "Pad_TP") (pintype "passive"))
      (node (ref "D58") (pin "TP") (pinfunction "Pad_TP") (pintype "passive"))
      (node (ref "D59") (pin "TP") (pinfunction "Pad_TP") (pintype "passive"))
      (node (ref "D6") (pin "TP") (pinfunction "Pad_TP") (pintype "passive"))
      (node (ref "D60") (pin "TP") (pinfunction "Pad_TP") (pintype "passive"))
      (node (ref "D61") (pin "TP") (pinfunction "Pad_TP") (pintype "passive"))
      (node (ref "D62") (pin "TP") (pinfunction "Pad_TP") (pintype "passive"))
      (node (ref "D63") (pin "TP") (pinfunction "Pad_TP") (pintype "passive"))
      (node (ref "D64") (pin "TP") (pinfunction "Pad_TP") (pintype "passive"))
      (node (ref "D65") (pin "TP") (pinfunction "Pad_TP") (pintype "passive"))
      (node (ref "D66") (pin "TP") (pinfunction "Pad_TP") (pintype "passive"))
      (node (ref "D67") (pin "TP") (pinfunction "Pad_TP") (pintype "passive"))
      (node (ref "D68") (pin "TP") (pinfunction "Pad_TP") (pintype "passive"))
      (node (ref "D69") (pin "TP") (pinfunction "Pad_TP") (pintype "passive"))
      (node (ref "D7") (pin "TP") (pinfunction "Pad_TP") (pintype "passive"))
      (node (ref "D70") (pin "TP") (pinfunction "Pad_TP") (pintype "passive"))
      (node (ref "D71") (pin "TP") (pinfunction "Pad_TP") (pintype "passive"))
      (node (ref "D72") (pin "TP") (pinfunction "Pad_TP") (pintype "passive"))
      (node (ref "D73") (pin "TP") (pinfunction "Pad_TP") (pintype "passive"))
      (node (ref "D74") (pin "TP") (pinfunction "Pad_TP") (pintype "passive"))
      (node (ref "D75") (pin "TP") (pinfunction "Pad_TP") (pintype "passive"))
      (node (ref "D76") (pin "TP") (pinfunction "Pad_TP") (pintype "passive"))
      (node (ref "D77") (pin "TP") (pinfunction "Pad_TP") (pintype "passive"))
      (node (ref "D78") (pin "TP") (pinfunction "Pad_TP") (pintype "passive"))
      (node (ref "D79") (pin "TP") (pinfunction "Pad_TP") (pintype "passive"))
      (node (ref "D8") (pin "TP") (pinfunction "Pad_TP") (pintype "passive"))
      (node (ref "D80") (pin "TP") (pinfunction "Pad_TP") (pintype "passive"))
      (node (ref "D81") (pin "TP") (pinfunction "Pad_TP") (pintype "passive"))
      (node (ref "D82") (pin "TP") (pinfunction "Pad_TP") (pintype "passive"))
      (node (ref "D83") (pin "TP") (pinfunction "Pad_TP") (pintype "passive"))
      (node (ref "D84") (pin "TP") (pinfunction "Pad_TP") (pintype "passive"))
      (node (ref "D85") (pin "TP") (pinfunction "Pad_TP") (pintype "passive"))
      (node (ref "D86") (pin "TP") (pinfunction "Pad_TP") (pintype "passive"))
      (node (ref "D87") (pin "TP") (pinfunction "Pad_TP") (pintype "passive"))
      (node (ref "D88") (pin "TP") (pinfunction "Pad_TP") (pintype "passive"))
      (node (ref "D89") (pin "TP") (pinfunction "Pad_TP") (pintype "passive"))
      (node (ref "D9") (pin "TP") (pinfunction "Pad_TP") (pintype "passive"))
      (node (ref "D90") (pin "TP") (pinfunction "Pad_TP") (pintype "passive"))
      (node (ref "D91") (pin "TP") (pinfunction "Pad_TP") (pintype "passive"))
      (node (ref "D92") (pin "TP") (pinfunction "Pad_TP") (pintype "passive"))
      (node (ref "D93") (pin "TP") (pinfunction "Pad_TP") (pintype "passive"))
      (node (ref "D94") (pin "TP") (pinfunction "Pad_TP") (pintype "passive"))
      (node (ref "D95") (pin "TP") (pinfunction "Pad_TP") (pintype "passive"))
      (node (ref "D96") (pin "TP") (pinfunction "Pad_TP") (pintype "passive"))
      (node (ref "D97") (pin "TP") (pinfunction "Pad_TP") (pintype "passive"))
      (node (ref "D98") (pin "TP") (pinfunction "Pad_TP") (pintype "passive"))
      (node (ref "D99") (pin "TP") (pinfunction "Pad_TP") (pintype "passive"))
    )
    (net (code "10") (name "Net-(D1-PadK)") (class "Default")
      (node (ref "D1") (pin "K") (pinfunction "K_K") (pintype "passive"))
      (node (ref "D2") (pin "A") (pinfunction "A_A") (pintype "passive"))
    )
    (net (code "11") (name "Net-(D2-PadK)") (class "Default")
      (node (ref "D2") (pin "K") (pinfunction "K_K") (pintype "passive"))
      (node (ref "D3") (pin "A") (pinfunction "A_A") (pintype "passive"))
    )
    (net (code "12") (name "Net-(D3-PadK)") (class "Default")
      (node (ref "D3") (pin "K") (pinfunction "K_K") (pintype "passive"))
      (node (ref "D4") (pin "A") (pinfunction "A_A") (pintype "passive"))
    )
    (net (code "13") (name "Net-(D4-PadK)") (class "Default")
      (node (ref "D4") (pin "K") (pinfunction "K_K") (pintype "passive"))
      (node (ref "D5") (pin "A") (pinfunction "A_A") (pintype "passive"))
    )
    (net (code "14") (name "Net-(D5-PadK)") (class "Default")
      (node (ref "D5") (pin "K") (pinfunction "K_K") (pintype "passive"))
      (node (ref "D6") (pin "A") (pinfunction "A_A") (pintype "passive"))
    )
    (net (code "15") (name "Net-(D6-PadK)") (class "Default")
      (node (ref "D6") (pin "K") (pinfunction "K_K") (pintype "passive"))
      (node (ref "D7") (pin "A") (pinfunction "A_A") (pintype "passive"))
    )
    (net (code "16") (name "Net-(D7-PadK)") (class "Default")
      (node (ref "D7") (pin "K") (pinfunction "K_K") (pintype "passive"))
      (node (ref "D8") (pin "A") (pinfunction "A_A") (pintype "passive"))
    )
    (net (code "17") (name "Net-(D10-PadA)") (class "Default")
      (node (ref "D10") (pin "A") (pinfunction "A_A") (pintype "passive"))
      (node (ref "D9") (pin "K") (pinfunction "K_K") (pintype "passive"))
    )
    (net (code "18") (name "Net-(D10-PadK)") (class "Default")
      (node (ref "D10") (pin "K") (pinfunction "K_K") (pintype "passive"))
      (node (ref "D11") (pin "A") (pinfunction "A_A") (pintype "passive"))
    )
    (net (code "19") (name "Net-(D11-PadK)") (class "Default")
      (node (ref "D11") (pin "K") (pinfunction "K_K") (pintype "passive"))
      (node (ref "D12") (pin "A") (pinfunction "A_A") (pintype "passive"))
    )
    (net (code "20") (name "Net-(D12-PadK)") (class "Default")
      (node (ref "D12") (pin "K") (pinfunction "K_K") (pintype "passive"))
      (node (ref "D13") (pin "A") (pinfunction "A_A") (pintype "passive"))
    )
    (net (code "21") (name "Net-(D13-PadK)") (class "Default")
      (node (ref "D13") (pin "K") (pinfunction "K_K") (pintype "passive"))
      (node (ref "D14") (pin "A") (pinfunction "A_A") (pintype "passive"))
    )
    (net (code "22") (name "Net-(D14-PadK)") (class "Default")
      (node (ref "D14") (pin "K") (pinfunction "K_K") (pintype "passive"))
      (node (ref "D15") (pin "A") (pinfunction "A_A") (pintype "passive"))
    )
    (net (code "23") (name "Net-(D15-PadK)") (class "Default")
      (node (ref "D15") (pin "K") (pinfunction "K_K") (pintype "passive"))
      (node (ref "D16") (pin "A") (pinfunction "A_A") (pintype "passive"))
    )
    (net (code "24") (name "Net-(D17-PadK)") (class "Default")
      (node (ref "D17") (pin "K") (pinfunction "K_K") (pintype "passive"))
      (node (ref "D18") (pin "A") (pinfunction "A_A") (pintype "passive"))
    )
    (net (code "25") (name "Net-(D18-PadK)") (class "Default")
      (node (ref "D18") (pin "K") (pinfunction "K_K") (pintype "passive"))
      (node (ref "D19") (pin "A") (pinfunction "A_A") (pintype "passive"))
    )
    (net (code "26") (name "Net-(D19-PadK)") (class "Default")
      (node (ref "D19") (pin "K") (pinfunction "K_K") (pintype "passive"))
      (node (ref "D20") (pin "A") (pinfunction "A_A") (pintype "passive"))
    )
    (net (code "27") (name "Net-(D20-PadK)") (class "Default")
      (node (ref "D20") (pin "K") (pinfunction "K_K") (pintype "passive"))
      (node (ref "D21") (pin "A") (pinfunction "A_A") (pintype "passive"))
    )
    (net (code "28") (name "Net-(D21-PadK)") (class "Default")
      (node (ref "D21") (pin "K") (pinfunction "K_K") (pintype "passive"))
      (node (ref "D22") (pin "A") (pinfunction "A_A") (pintype "passive"))
    )
    (net (code "29") (name "Net-(D22-PadK)") (class "Default")
      (node (ref "D22") (pin "K") (pinfunction "K_K") (pintype "passive"))
      (node (ref "D23") (pin "A") (pinfunction "A_A") (pintype "passive"))
    )
    (net (code "30") (name "Net-(D23-PadK)") (class "Default")
      (node (ref "D23") (pin "K") (pinfunction "K_K") (pintype "passive"))
      (node (ref "D24") (pin "A") (pinfunction "A_A") (pintype "passive"))
    )
    (net (code "31") (name "Net-(D25-PadK)") (class "Default")
      (node (ref "D25") (pin "K") (pinfunction "K_K") (pintype "passive"))
      (node (ref "D26") (pin "A") (pinfunction "A_A") (pintype "passive"))
    )
    (net (code "32") (name "Net-(D26-PadK)") (class "Default")
      (node (ref "D26") (pin "K") (pinfunction "K_K") (pintype "passive"))
      (node (ref "D27") (pin "A") (pinfunction "A_A") (pintype "passive"))
    )
    (net (code "33") (name "Net-(D27-PadK)") (class "Default")
      (node (ref "D27") (pin "K") (pinfunction "K_K") (pintype "passive"))
      (node (ref "D28") (pin "A") (pinfunction "A_A") (pintype "passive"))
    )
    (net (code "34") (name "Net-(D28-PadK)") (class "Default")
      (node (ref "D28") (pin "K") (pinfunction "K_K") (pintype "passive"))
      (node (ref "D29") (pin "A") (pinfunction "A_A") (pintype "passive"))
    )
    (net (code "35") (name "Net-(D29-PadK)") (class "Default")
      (node (ref "D29") (pin "K") (pinfunction "K_K") (pintype "passive"))
      (node (ref "D30") (pin "A") (pinfunction "A_A") (pintype "passive"))
    )
    (net (code "36") (name "Net-(D30-PadK)") (class "Default")
      (node (ref "D30") (pin "K") (pinfunction "K_K") (pintype "passive"))
      (node (ref "D31") (pin "A") (pinfunction "A_A") (pintype "passive"))
    )
    (net (code "37") (name "Net-(D31-PadK)") (class "Default")
      (node (ref "D31") (pin "K") (pinfunction "K_K") (pintype "passive"))
      (node (ref "D32") (pin "A") (pinfunction "A_A") (pintype "passive"))
    )
    (net (code "38") (name "Net-(D33-PadK)") (class "Default")
      (node (ref "D33") (pin "K") (pinfunction "K_K") (pintype "passive"))
      (node (ref "D34") (pin "A") (pinfunction "A_A") (pintype "passive"))
    )
    (net (code "39") (name "Net-(D34-PadK)") (class "Default")
      (node (ref "D34") (pin "K") (pinfunction "K_K") (pintype "passive"))
      (node (ref "D35") (pin "A") (pinfunction "A_A") (pintype "passive"))
    )
    (net (code "40") (name "Net-(D35-PadK)") (class "Default")
      (node (ref "D35") (pin "K") (pinfunction "K_K") (pintype "passive"))
      (node (ref "D36") (pin "A") (pinfunction "A_A") (pintype "passive"))
    )
    (net (code "41") (name "Net-(D36-PadK)") (class "Default")
      (node (ref "D36") (pin "K") (pinfunction "K_K") (pintype "passive"))
      (node (ref "D37") (pin "A") (pinfunction "A_A") (pintype "passive"))
    )
    (net (code "42") (name "Net-(D37-PadK)") (class "Default")
      (node (ref "D37") (pin "K") (pinfunction "K_K") (pintype "passive"))
      (node (ref "D38") (pin "A") (pinfunction "A_A") (pintype "passive"))
    )
    (net (code "43") (name "Net-(D38-PadK)") (class "Default")
      (node (ref "D38") (pin "K") (pinfunction "K_K") (pintype "passive"))
      (node (ref "D39") (pin "A") (pinfunction "A_A") (pintype "passive"))
    )
    (net (code "44") (name "Net-(D39-PadK)") (class "Default")
      (node (ref "D39") (pin "K") (pinfunction "K_K") (pintype "passive"))
      (node (ref "D40") (pin "A") (pinfunction "A_A") (pintype "passive"))
    )
    (net (code "45") (name "Net-(D41-PadK)") (class "Default")
      (node (ref "D41") (pin "K") (pinfunction "K_K") (pintype "passive"))
      (node (ref "D42") (pin "A") (pinfunction "A_A") (pintype "passive"))
    )
    (net (code "46") (name "Net-(D42-PadK)") (class "Default")
      (node (ref "D42") (pin "K") (pinfunction "K_K") (pintype "passive"))
      (node (ref "D43") (pin "A") (pinfunction "A_A") (pintype "passive"))
    )
    (net (code "47") (name "Net-(D43-PadK)") (class "Default")
      (node (ref "D43") (pin "K") (pinfunction "K_K") (pintype "passive"))
      (node (ref "D44") (pin "A") (pinfunction "A_A") (pintype "passive"))
    )
    (net (code "48") (name "Net-(D44-PadK)") (class "Default")
      (node (ref "D44") (pin "K") (pinfunction "K_K") (pintype "passive"))
      (node (ref "D45") (pin "A") (pinfunction "A_A") (pintype "passive"))
    )
    (net (code "49") (name "Net-(D45-PadK)") (class "Default")
      (node (ref "D45") (pin "K") (pinfunction "K_K") (pintype "passive"))
      (node (ref "D46") (pin "A") (pinfunction "A_A") (pintype "passive"))
    )
    (net (code "50") (name "Net-(D46-PadK)") (class "Default")
      (node (ref "D46") (pin "K") (pinfunction "K_K") (pintype "passive"))
      (node (ref "D47") (pin "A") (pinfunction "A_A") (pintype "passive"))
    )
    (net (code "51") (name "Net-(D47-PadK)") (class "Default")
      (node (ref "D47") (pin "K") (pinfunction "K_K") (pintype "passive"))
      (node (ref "D48") (pin "A") (pinfunction "A_A") (pintype "passive"))
    )
    (net (code "52") (name "Net-(D49-PadK)") (class "Default")
      (node (ref "D49") (pin "K") (pinfunction "K_K") (pintype "passive"))
      (node (ref "D50") (pin "A") (pinfunction "A_A") (pintype "passive"))
    )
    (net (code "53") (name "Net-(D50-PadK)") (class "Default")
      (node (ref "D50") (pin "K") (pinfunction "K_K") (pintype "passive"))
      (node (ref "D51") (pin "A") (pinfunction "A_A") (pintype "passive"))
    )
    (net (code "54") (name "Net-(D51-PadK)") (class "Default")
      (node (ref "D51") (pin "K") (pinfunction "K_K") (pintype "passive"))
      (node (ref "D52") (pin "A") (pinfunction "A_A") (pintype "passive"))
    )
    (net (code "55") (name "Net-(D52-PadK)") (class "Default")
      (node (ref "D52") (pin "K") (pinfunction "K_K") (pintype "passive"))
      (node (ref "D53") (pin "A") (pinfunction "A_A") (pintype "passive"))
    )
    (net (code "56") (name "Net-(D53-PadK)") (class "Default")
      (node (ref "D53") (pin "K") (pinfunction "K_K") (pintype "passive"))
      (node (ref "D54") (pin "A") (pinfunction "A_A") (pintype "passive"))
    )
    (net (code "57") (name "Net-(D54-PadK)") (class "Default")
      (node (ref "D54") (pin "K") (pinfunction "K_K") (pintype "passive"))
      (node (ref "D55") (pin "A") (pinfunction "A_A") (pintype "passive"))
    )
    (net (code "58") (name "Net-(D55-PadK)") (class "Default")
      (node (ref "D55") (pin "K") (pinfunction "K_K") (pintype "passive"))
      (node (ref "D56") (pin "A") (pinfunction "A_A") (pintype "passive"))
    )
    (net (code "59") (name "Net-(D57-PadK)") (class "Default")
      (node (ref "D57") (pin "K") (pinfunction "K_K") (pintype "passive"))
      (node (ref "D58") (pin "A") (pinfunction "A_A") (pintype "passive"))
    )
    (net (code "60") (name "Net-(D58-PadK)") (class "Default")
      (node (ref "D58") (pin "K") (pinfunction "K_K") (pintype "passive"))
      (node (ref "D59") (pin "A") (pinfunction "A_A") (pintype "passive"))
    )
    (net (code "61") (name "Net-(D59-PadK)") (class "Default")
      (node (ref "D59") (pin "K") (pinfunction "K_K") (pintype "passive"))
      (node (ref "D60") (pin "A") (pinfunction "A_A") (pintype "passive"))
    )
    (net (code "62") (name "Net-(D60-PadK)") (class "Default")
      (node (ref "D60") (pin "K") (pinfunction "K_K") (pintype "passive"))
      (node (ref "D61") (pin "A") (pinfunction "A_A") (pintype "passive"))
    )
    (net (code "63") (name "Net-(D61-PadK)") (class "Default")
      (node (ref "D61") (pin "K") (pinfunction "K_K") (pintype "passive"))
      (node (ref "D62") (pin "A") (pinfunction "A_A") (pintype "passive"))
    )
    (net (code "64") (name "Net-(D62-PadK)") (class "Default")
      (node (ref "D62") (pin "K") (pinfunction "K_K") (pintype "passive"))
      (node (ref "D63") (pin "A") (pinfunction "A_A") (pintype "passive"))
    )
    (net (code "65") (name "Net-(D63-PadK)") (class "Default")
      (node (ref "D63") (pin "K") (pinfunction "K_K") (pintype "passive"))
      (node (ref "D64") (pin "A") (pinfunction "A_A") (pintype "passive"))
    )
    (net (code "66") (name "Net-(D65-PadK)") (class "Default")
      (node (ref "D65") (pin "K") (pinfunction "K_K") (pintype "passive"))
      (node (ref "D66") (pin "A") (pinfunction "A_A") (pintype "passive"))
    )
    (net (code "67") (name "Net-(D66-PadK)") (class "Default")
      (node (ref "D66") (pin "K") (pinfunction "K_K") (pintype "passive"))
      (node (ref "D67") (pin "A") (pinfunction "A_A") (pintype "passive"))
    )
    (net (code "68") (name "Net-(D67-PadK)") (class "Default")
      (node (ref "D67") (pin "K") (pinfunction "K_K") (pintype "passive"))
      (node (ref "D68") (pin "A") (pinfunction "A_A") (pintype "passive"))
    )
    (net (code "69") (name "Net-(D68-PadK)") (class "Default")
      (node (ref "D68") (pin "K") (pinfunction "K_K") (pintype "passive"))
      (node (ref "D69") (pin "A") (pinfunction "A_A") (pintype "passive"))
    )
    (net (code "70") (name "Net-(D69-PadK)") (class "Default")
      (node (ref "D69") (pin "K") (pinfunction "K_K") (pintype "passive"))
      (node (ref "D70") (pin "A") (pinfunction "A_A") (pintype "passive"))
    )
    (net (code "71") (name "Net-(D70-PadK)") (class "Default")
      (node (ref "D70") (pin "K") (pinfunction "K_K") (pintype "passive"))
      (node (ref "D71") (pin "A") (pinfunction "A_A") (pintype "passive"))
    )
    (net (code "72") (name "Net-(D71-PadK)") (class "Default")
      (node (ref "D71") (pin "K") (pinfunction "K_K") (pintype "passive"))
      (node (ref "D72") (pin "A") (pinfunction "A_A") (pintype "passive"))
    )
    (net (code "73") (name "Net-(D73-PadK)") (class "Default")
      (node (ref "D73") (pin "K") (pinfunction "K_K") (pintype "passive"))
      (node (ref "D74") (pin "A") (pinfunction "A_A") (pintype "passive"))
    )
    (net (code "74") (name "Net-(D74-PadK)") (class "Default")
      (node (ref "D74") (pin "K") (pinfunction "K_K") (pintype "passive"))
      (node (ref "D75") (pin "A") (pinfunction "A_A") (pintype "passive"))
    )
    (net (code "75") (name "Net-(D75-PadK)") (class "Default")
      (node (ref "D75") (pin "K") (pinfunction "K_K") (pintype "passive"))
      (node (ref "D76") (pin "A") (pinfunction "A_A") (pintype "passive"))
    )
    (net (code "76") (name "Net-(D76-PadK)") (class "Default")
      (node (ref "D76") (pin "K") (pinfunction "K_K") (pintype "passive"))
      (node (ref "D77") (pin "A") (pinfunction "A_A") (pintype "passive"))
    )
    (net (code "77") (name "Net-(D77-PadK)") (class "Default")
      (node (ref "D77") (pin "K") (pinfunction "K_K") (pintype "passive"))
      (node (ref "D78") (pin "A") (pinfunction "A_A") (pintype "passive"))
    )
    (net (code "78") (name "Net-(D78-PadK)") (class "Default")
      (node (ref "D78") (pin "K") (pinfunction "K_K") (pintype "passive"))
      (node (ref "D79") (pin "A") (pinfunction "A_A") (pintype "passive"))
    )
    (net (code "79") (name "Net-(D79-PadK)") (class "Default")
      (node (ref "D79") (pin "K") (pinfunction "K_K") (pintype "passive"))
      (node (ref "D80") (pin "A") (pinfunction "A_A") (pintype "passive"))
    )
    (net (code "80") (name "Net-(D81-PadK)") (class "Default")
      (node (ref "D81") (pin "K") (pinfunction "K_K") (pintype "passive"))
      (node (ref "D82") (pin "A") (pinfunction "A_A") (pintype "passive"))
    )
    (net (code "81") (name "Net-(D82-PadK)") (class "Default")
      (node (ref "D82") (pin "K") (pinfunction "K_K") (pintype "passive"))
      (node (ref "D83") (pin "A") (pinfunction "A_A") (pintype "passive"))
    )
    (net (code "82") (name "Net-(D83-PadK)") (class "Default")
      (node (ref "D83") (pin "K") (pinfunction "K_K") (pintype "passive"))
      (node (ref "D84") (pin "A") (pinfunction "A_A") (pintype "passive"))
    )
    (net (code "83") (name "Net-(D84-PadK)") (class "Default")
      (node (ref "D84") (pin "K") (pinfunction "K_K") (pintype "passive"))
      (node (ref "D85") (pin "A") (pinfunction "A_A") (pintype "passive"))
    )
    (net (code "84") (name "Net-(D85-PadK)") (class "Default")
      (node (ref "D85") (pin "K") (pinfunction "K_K") (pintype "passive"))
      (node (ref "D86") (pin "A") (pinfunction "A_A") (pintype "passive"))
    )
    (net (code "85") (name "Net-(D86-PadK)") (class "Default")
      (node (ref "D86") (pin "K") (pinfunction "K_K") (pintype "passive"))
      (node (ref "D87") (pin "A") (pinfunction "A_A") (pintype "passive"))
    )
    (net (code "86") (name "Net-(D87-PadK)") (class "Default")
      (node (ref "D87") (pin "K") (pinfunction "K_K") (pintype "passive"))
      (node (ref "D88") (pin "A") (pinfunction "A_A") (pintype "passive"))
    )
    (net (code "87") (name "Net-(D89-PadK)") (class "Default")
      (node (ref "D89") (pin "K") (pinfunction "K_K") (pintype "passive"))
      (node (ref "D90") (pin "A") (pinfunction "A_A") (pintype "passive"))
    )
    (net (code "88") (name "Net-(D90-PadK)") (class "Default")
      (node (ref "D90") (pin "K") (pinfunction "K_K") (pintype "passive"))
      (node (ref "D91") (pin "A") (pinfunction "A_A") (pintype "passive"))
    )
    (net (code "89") (name "Net-(D91-PadK)") (class "Default")
      (node (ref "D91") (pin "K") (pinfunction "K_K") (pintype "passive"))
      (node (ref "D92") (pin "A") (pinfunction "A_A") (pintype "passive"))
    )
    (net (code "90") (name "Net-(D92-PadK)") (class "Default")
      (node (ref "D92") (pin "K") (pinfunction "K_K") (pintype "passive"))
      (node (ref "D93") (pin "A") (pinfunction "A_A") (pintype "passive"))
    )
    (net (code "91") (name "Net-(D93-PadK)") (class "Default")
      (node (ref "D93") (pin "K") (pinfunction "K_K") (pintype "passive"))
      (node (ref "D94") (pin "A") (pinfunction "A_A") (pintype "passive"))
    )
    (net (code "92") (name "Net-(D94-PadK)") (class "Default")
      (node (ref "D94") (pin "K") (pinfunction "K_K") (pintype "passive"))
      (node (ref "D95") (pin "A") (pinfunction "A_A") (pintype "passive"))
    )
    (net (code "93") (name "Net-(D95-PadK)") (class "Default")
      (node (ref "D95") (pin "K") (pinfunction "K_K") (pintype "passive"))
      (node (ref "D96") (pin "A") (pinfunction "A_A") (pintype "passive"))
    )
    (net (code "94") (name "Net-(D97-PadK)") (class "Default")
      (node (ref "D97") (pin "K") (pinfunction "K_K") (pintype "passive"))
      (node (ref "D98") (pin "A") (pinfunction "A_A") (pintype "passive"))
    )
    (net (code "95") (name "Net-(D98-PadK)") (class "Default")
      (node (ref "D98") (pin "K") (pinfunction "K_K") (pintype "passive"))
      (node (ref "D99") (pin "A") (pinfunction "A_A") (pintype "passive"))
    )
    (net (code "96") (name "Net-(D100-PadA)") (class "Default")
      (node (ref "D100") (pin "A") (pinfunction "A_A") (pintype "passive"))
      (node (ref "D99") (pin "K") (pinfunction "K_K") (pintype "passive"))
    )
    (net (code "97") (name "Net-(D100-PadK)") (class "Default")
      (node (ref "D100") (pin "K") (pinfunction "K_K") (pintype "passive"))
      (node (ref "D101") (pin "A") (pinfunction "A_A") (pintype "passive"))
    )
    (net (code "98") (name "Net-(D101-PadK)") (class "Default")
      (node (ref "D101") (pin "K") (pinfunction "K_K") (pintype "passive"))
      (node (ref "D102") (pin "A") (pinfunction "A_A") (pintype "passive"))
    )
    (net (code "99") (name "Net-(D102-PadK)") (class "Default")
      (node (ref "D102") (pin "K") (pinfunction "K_K") (pintype "passive"))
      (node (ref "D103") (pin "A") (pinfunction "A_A") (pintype "passive"))
    )
    (net (code "100") (name "Net-(D103-PadK)") (class "Default")
      (node (ref "D103") (pin "K") (pinfunction "K_K") (pintype "passive"))
      (node (ref "D104") (pin "A") (pinfunction "A_A") (pintype "passive"))
    )
    (net (code "101") (name "Net-(D105-PadK)") (class "Default")
      (node (ref "D105") (pin "K") (pinfunction "K_K") (pintype "passive"))
      (node (ref "D106") (pin "A") (pinfunction "A_A") (pintype "passive"))
    )
    (net (code "102") (name "Net-(D106-PadK)") (class "Default")
      (node (ref "D106") (pin "K") (pinfunction "K_K") (pintype "passive"))
      (node (ref "D107") (pin "A") (pinfunction "A_A") (pintype "passive"))
    )
    (net (code "103") (name "Net-(D107-PadK)") (class "Default")
      (node (ref "D107") (pin "K") (pinfunction "K_K") (pintype "passive"))
      (node (ref "D108") (pin "A") (pinfunction "A_A") (pintype "passive"))
    )
    (net (code "104") (name "Net-(D108-PadK)") (class "Default")
      (node (ref "D108") (pin "K") (pinfunction "K_K") (pintype "passive"))
      (node (ref "D109") (pin "A") (pinfunction "A_A") (pintype "passive"))
    )
    (net (code "105") (name "Net-(D109-PadK)") (class "Default")
      (node (ref "D109") (pin "K") (pinfunction "K_K") (pintype "passive"))
      (node (ref "D110") (pin "A") (pinfunction "A_A") (pintype "passive"))
    )
    (net (code "106") (name "Net-(D110-PadK)") (class "Default")
      (node (ref "D110") (pin "K") (pinfunction "K_K") (pintype "passive"))
      (node (ref "D111") (pin "A") (pinfunction "A_A") (pintype "passive"))
    )
    (net (code "107") (name "Net-(D111-PadK)") (class "Default")
      (node (ref "D111") (pin "K") (pinfunction "K_K") (pintype "passive"))
      (node (ref "D112") (pin "A") (pinfunction "A_A") (pintype "passive"))
    )
    (net (code "108") (name "Net-(D113-PadK)") (class "Default")
      (node (ref "D113") (pin "K") (pinfunction "K_K") (pintype "passive"))
      (node (ref "D114") (pin "A") (pinfunction "A_A") (pintype "passive"))
    )
    (net (code "109") (name "Net-(D114-PadK)") (class "Default")
      (node (ref "D114") (pin "K") (pinfunction "K_K") (pintype "passive"))
      (node (ref "D115") (pin "A") (pinfunction "A_A") (pintype "passive"))
    )
    (net (code "110") (name "Net-(D115-PadK)") (class "Default")
      (node (ref "D115") (pin "K") (pinfunction "K_K") (pintype "passive"))
      (node (ref "D116") (pin "A") (pinfunction "A_A") (pintype "passive"))
    )
    (net (code "111") (name "Net-(D116-PadK)") (class "Default")
      (node (ref "D116") (pin "K") (pinfunction "K_K") (pintype "passive"))
      (node (ref "D117") (pin "A") (pinfunction "A_A") (pintype "passive"))
    )
    (net (code "112") (name "Net-(D117-PadK)") (class "Default")
      (node (ref "D117") (pin "K") (pinfunction "K_K") (pintype "passive"))
      (node (ref "D118") (pin "A") (pinfunction "A_A") (pintype "passive"))
    )
    (net (code "113") (name "Net-(D118-PadK)") (class "Default")
      (node (ref "D118") (pin "K") (pinfunction "K_K") (pintype "passive"))
      (node (ref "D119") (pin "A") (pinfunction "A_A") (pintype "passive"))
    )
    (net (code "114") (name "Net-(D119-PadK)") (class "Default")
      (node (ref "D119") (pin "K") (pinfunction "K_K") (pintype "passive"))
      (node (ref "D120") (pin "A") (pinfunction "A_A") (pintype "passive"))
    )
    (net (code "115") (name "Net-(D121-PadK)") (class "Default")
      (node (ref "D121") (pin "K") (pinfunction "K_K") (pintype "passive"))
      (node (ref "D122") (pin "A") (pinfunction "A_A") (pintype "passive"))
    )
    (net (code "116") (name "Net-(D122-PadK)") (class "Default")
      (node (ref "D122") (pin "K") (pinfunction "K_K") (pintype "passive"))
      (node (ref "D123") (pin "A") (pinfunction "A_A") (pintype "passive"))
    )
    (net (code "117") (name "Net-(D123-PadK)") (class "Default")
      (node (ref "D123") (pin "K") (pinfunction "K_K") (pintype "passive"))
      (node (ref "D124") (pin "A") (pinfunction "A_A") (pintype "passive"))
    )
    (net (code "118") (name "Net-(D124-PadK)") (class "Default")
      (node (ref "D124") (pin "K") (pinfunction "K_K") (pintype "passive"))
      (node (ref "D125") (pin "A") (pinfunction "A_A") (pintype "passive"))
    )
    (net (code "119") (name "Net-(D125-PadK)") (class "Default")
      (node (ref "D125") (pin "K") (pinfunction "K_K") (pintype "passive"))
      (node (ref "D126") (pin "A") (pinfunction "A_A") (pintype "passive"))
    )
    (net (code "120") (name "Net-(D126-PadK)") (class "Default")
      (node (ref "D126") (pin "K") (pinfunction "K_K") (pintype "passive"))
      (node (ref "D127") (pin "A") (pinfunction "A_A") (pintype "passive"))
    )
    (net (code "121") (name "Net-(D127-PadK)") (class "Default")
      (node (ref "D127") (pin "K") (pinfunction "K_K") (pintype "passive"))
      (node (ref "D128") (pin "A") (pinfunction "A_A") (pintype "passive"))
    )
    (net (code "122") (name "Net-(D129-PadK)") (class "Default")
      (node (ref "D129") (pin "K") (pinfunction "K_K") (pintype "passive"))
      (node (ref "D130") (pin "A") (pinfunction "A_A") (pintype "passive"))
    )
    (net (code "123") (name "Net-(D130-PadK)") (class "Default")
      (node (ref "D130") (pin "K") (pinfunction "K_K") (pintype "passive"))
      (node (ref "D131") (pin "A") (pinfunction "A_A") (pintype "passive"))
    )
    (net (code "124") (name "Net-(D131-PadK)") (class "Default")
      (node (ref "D131") (pin "K") (pinfunction "K_K") (pintype "passive"))
      (node (ref "D132") (pin "A") (pinfunction "A_A") (pintype "passive"))
    )
    (net (code "125") (name "Net-(D132-PadK)") (class "Default")
      (node (ref "D132") (pin "K") (pinfunction "K_K") (pintype "passive"))
      (node (ref "D133") (pin "A") (pinfunction "A_A") (pintype "passive"))
    )
    (net (code "126") (name "Net-(D133-PadK)") (class "Default")
      (node (ref "D133") (pin "K") (pinfunction "K_K") (pintype "passive"))
      (node (ref "D134") (pin "A") (pinfunction "A_A") (pintype "passive"))
    )
    (net (code "127") (name "Net-(D134-PadK)") (class "Default")
      (node (ref "D134") (pin "K") (pinfunction "K_K") (pintype "passive"))
      (node (ref "D135") (pin "A") (pinfunction "A_A") (pintype "passive"))
    )
    (net (code "128") (name "Net-(D135-PadK)") (class "Default")
      (node (ref "D135") (pin "K") (pinfunction "K_K") (pintype "passive"))
      (node (ref "D136") (pin "A") (pinfunction "A_A") (pintype "passive"))
    )
    (net (code "129") (name "Net-(D137-PadK)") (class "Default")
      (node (ref "D137") (pin "K") (pinfunction "K_K") (pintype "passive"))
      (node (ref "D138") (pin "A") (pinfunction "A_A") (pintype "passive"))
    )
    (net (code "130") (name "Net-(D138-PadK)") (class "Default")
      (node (ref "D138") (pin "K") (pinfunction "K_K") (pintype "passive"))
      (node (ref "D139") (pin "A") (pinfunction "A_A") (pintype "passive"))
    )
    (net (code "131") (name "Net-(D139-PadK)") (class "Default")
      (node (ref "D139") (pin "K") (pinfunction "K_K") (pintype "passive"))
      (node (ref "D140") (pin "A") (pinfunction "A_A") (pintype "passive"))
    )
    (net (code "132") (name "Net-(D140-PadK)") (class "Default")
      (node (ref "D140") (pin "K") (pinfunction "K_K") (pintype "passive"))
      (node (ref "D141") (pin "A") (pinfunction "A_A") (pintype "passive"))
    )
    (net (code "133") (name "Net-(D141-PadK)") (class "Default")
      (node (ref "D141") (pin "K") (pinfunction "K_K") (pintype "passive"))
      (node (ref "D142") (pin "A") (pinfunction "A_A") (pintype "passive"))
    )
    (net (code "134") (name "Net-(D142-PadK)") (class "Default")
      (node (ref "D142") (pin "K") (pinfunction "K_K") (pintype "passive"))
      (node (ref "D143") (pin "A") (pinfunction "A_A") (pintype "passive"))
    )
    (net (code "135") (name "Net-(D143-PadK)") (class "Default")
      (node (ref "D143") (pin "K") (pinfunction "K_K") (pintype "passive"))
      (node (ref "D144") (pin "A") (pinfunction "A_A") (pintype "passive"))
    )
    (net (code "136") (name "Net-(J1-K1)") (class "Default")
      (node (ref "D8") (pin "K") (pinfunction "K_K") (pintype "passive"))
      (node (ref "J1") (pin "7") (pinfunction "K1_7") (pintype "passive"))
    )
    (net (code "137") (name "Net-(J1-K2)") (class "Default")
      (node (ref "D16") (pin "K") (pinfunction "K_K") (pintype "passive"))
      (node (ref "J1") (pin "6") (pinfunction "K2_6") (pintype "passive"))
    )
    (net (code "138") (name "Net-(J1-K3)") (class "Default")
      (node (ref "D24") (pin "K") (pinfunction "K_K") (pintype "passive"))
      (node (ref "J1") (pin "5") (pinfunction "K3_5") (pintype "passive"))
    )
    (net (code "139") (name "Net-(J1-K4)") (class "Default")
      (node (ref "D32") (pin "K") (pinfunction "K_K") (pintype "passive"))
      (node (ref "J1") (pin "4") (pinfunction "K4_4") (pintype "passive"))
    )
    (net (code "140") (name "Net-(J1-K5)") (class "Default")
      (node (ref "D40") (pin "K") (pinfunction "K_K") (pintype "passive"))
      (node (ref "J1") (pin "3") (pinfunction "K5_3") (pintype "passive"))
    )
    (net (code "141") (name "Net-(J1-K6)") (class "Default")
      (node (ref "D48") (pin "K") (pinfunction "K_K") (pintype "passive"))
      (node (ref "J1") (pin "2") (pinfunction "K6_2") (pintype "passive"))
    )
    (net (code "142") (name "Net-(J2-K1)") (class "Default")
      (node (ref "D56") (pin "K") (pinfunction "K_K") (pintype "passive"))
      (node (ref "J2") (pin "7") (pinfunction "K1_7") (pintype "passive"))
    )
    (net (code "143") (name "Net-(J2-K2)") (class "Default")
      (node (ref "D64") (pin "K") (pinfunction "K_K") (pintype "passive"))
      (node (ref "J2") (pin "6") (pinfunction "K2_6") (pintype "passive"))
    )
    (net (code "144") (name "Net-(J2-K3)") (class "Default")
      (node (ref "D72") (pin "K") (pinfunction "K_K") (pintype "passive"))
      (node (ref "J2") (pin "5") (pinfunction "K3_5") (pintype "passive"))
    )
    (net (code "145") (name "Net-(J2-K4)") (class "Default")
      (node (ref "D80") (pin "K") (pinfunction "K_K") (pintype "passive"))
      (node (ref "J2") (pin "4") (pinfunction "K4_4") (pintype "passive"))
    )
    (net (code "146") (name "Net-(J2-K5)") (class "Default")
      (node (ref "D88") (pin "K") (pinfunction "K_K") (pintype "passive"))
      (node (ref "J2") (pin "3") (pinfunction "K5_3") (pintype "passive"))
    )
    (net (code "147") (name "Net-(J2-K6)") (class "Default")
      (node (ref "D96") (pin "K") (pinfunction "K_K") (pintype "passive"))
      (node (ref "J2") (pin "2") (pinfunction "K6_2") (pintype "passive"))
    )
    (net (code "148") (name "Net-(J3-K1)") (class "Default")
      (node (ref "D104") (pin "K") (pinfunction "K_K") (pintype "passive"))
      (node (ref "J3") (pin "7") (pinfunction "K1_7") (pintype "passive"))
    )
    (net (code "149") (name "Net-(J3-K2)") (class "Default")
      (node (ref "D112") (pin "K") (pinfunction "K_K") (pintype "passive"))
      (node (ref "J3") (pin "6") (pinfunction "K2_6") (pintype "passive"))
    )
    (net (code "150") (name "Net-(J3-K3)") (class "Default")
      (node (ref "D120") (pin "K") (pinfunction "K_K") (pintype "passive"))
      (node (ref "J3") (pin "5") (pinfunction "K3_5") (pintype "passive"))
    )
    (net (code "151") (name "Net-(J3-K4)") (class "Default")
      (node (ref "D128") (pin "K") (pinfunction "K_K") (pintype "passive"))
      (node (ref "J3") (pin "4") (pinfunction "K4_4") (pintype "passive"))
    )
    (net (code "152") (name "Net-(J3-K5)") (class "Default")
      (node (ref "D136") (pin "K") (pinfunction "K_K") (pintype "passive"))
      (node (ref "J3") (pin "3") (pinfunction "K5_3") (pintype "passive"))
    )
    (net (code "153") (name "Net-(J3-K6)") (class "Default")
      (node (ref "D144") (pin "K") (pinfunction "K_K") (pintype "passive"))
      (node (ref "J3") (pin "2") (pinfunction "K6_2") (pintype "passive"))
    )
  )
)
